# ECG_TRUE.net
KiCad netlist of a schematic drawn in EAGLE
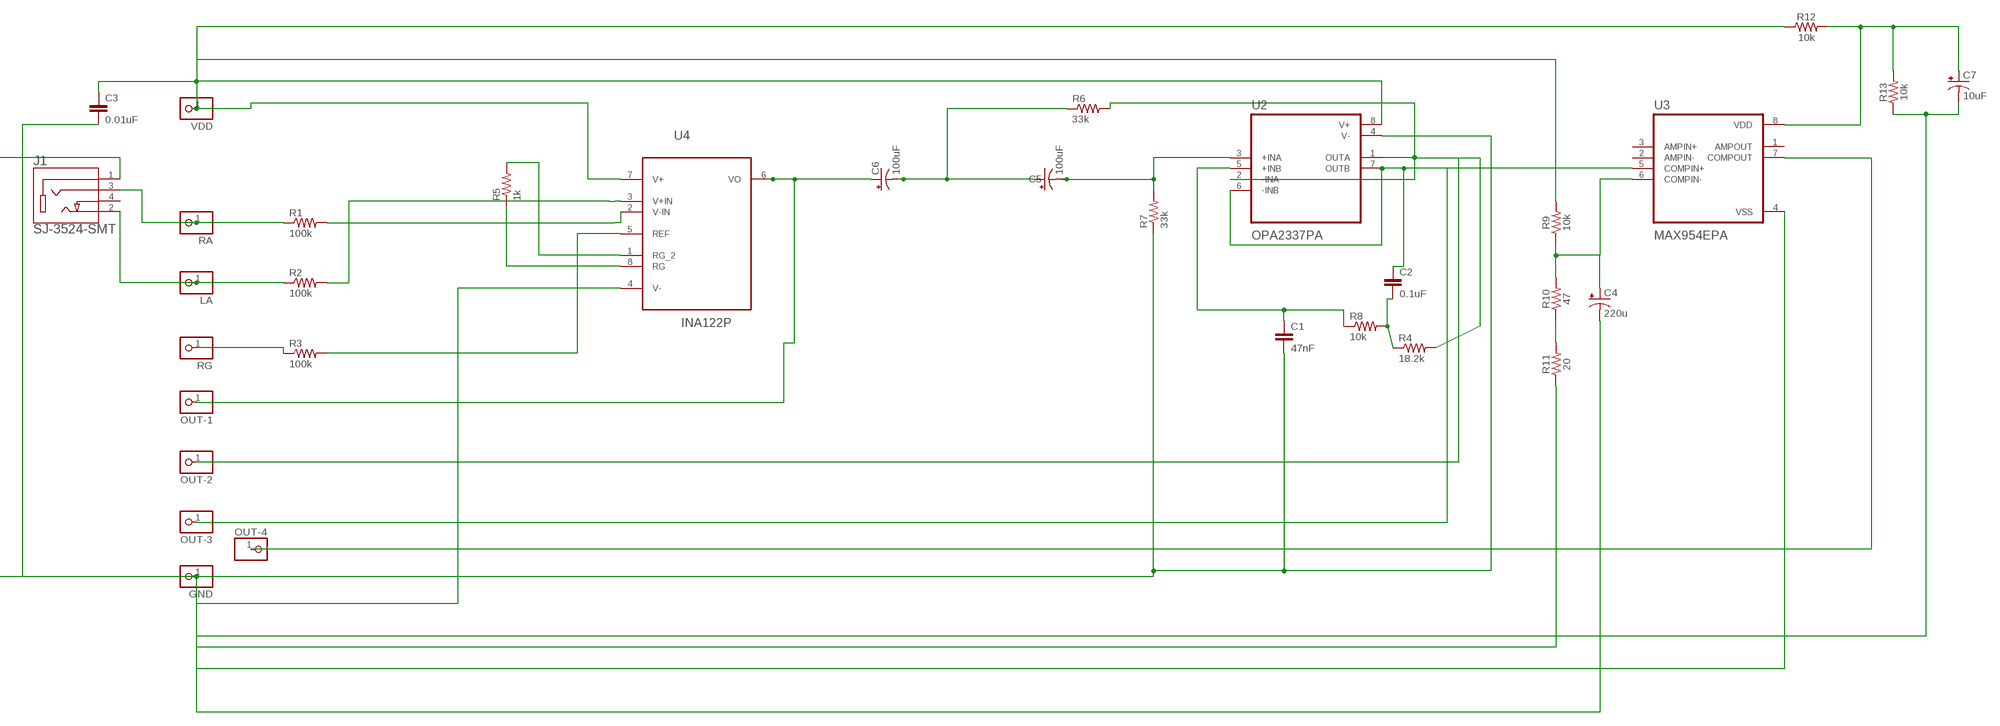
[diagram p0: schematic, sheet 1]

(export (version "E")
  (design (tool "Eeschema 10.0.6"))
  (components
    (comp (ref "C1")
      (value "47nF")
      (footprint "eagle-import:CAP-PTH-SMALL-KIT")
      (libsource (lib "eagle-import") (part "0.1UF-KIT-EZ-50V-20%"))
    )
    (comp (ref "C2")
      (value "0.1uF")
      (footprint "eagle-import:CAP-PTH-SMALL-KIT")
      (libsource (lib "eagle-import") (part "0.1UF-KIT-EZ-50V-20%"))
    )
    (comp (ref "C3")
      (value "0.01uF")
      (footprint "eagle-import:CAP-PTH-SMALL-KIT")
      (libsource (lib "eagle-import") (part "0.1UF-KIT-EZ-50V-20%"))
    )
    (comp (ref "C4")
      (value "220u")
      (footprint "eagle-import:E3,5-10")
      (libsource (lib "eagle-import") (part "CAPACITOR-PE3.5-10"))
    )
    (comp (ref "C5")
      (value "100uF")
      (footprint "eagle-import:CPOL-RADIAL-2.5MM-6.5MM")
      (libsource (lib "eagle-import") (part "100UF-POLAR-RADIAL-2.5MM-25V-20%"))
    )
    (comp (ref "C6")
      (value "100uF")
      (footprint "eagle-import:CPOL-RADIAL-2.5MM-6.5MM")
      (libsource (lib "eagle-import") (part "100UF-POLAR-RADIAL-2.5MM-25V-20%"))
    )
    (comp (ref "C7")
      (value "10uF")
      (footprint "eagle-import:CPOL-RADIAL-2.5MM-5MM-KIT")
      (libsource (lib "eagle-import") (part "10UF-POLAR-RADIAL-2.5MM-KIT-25V-20%"))
    )
    (comp (ref "GND")
      (value "PINHD-1X1")
      (footprint "eagle-import:1X01")
      (libsource (lib "eagle-import") (part "PINHD-1X1"))
    )
    (comp (ref "J1")
      (value "SJ-3524-SMT")
      (footprint "eagle-import:CUI_SJ-3524-SMT")
      (fields
        (field (name "DIGI-KEY_PART_NUMBER") "CP-3524SJCT-ND")
        (field (name "MF") "CUI Devices")
        (field (name "MP") "SJ-3524-SMT-TR")
      )
      (libsource (lib "eagle-import") (part "SJ-3524-SMT"))
    )
    (comp (ref "LA")
      (value "PINHD-1X1")
      (footprint "eagle-import:1X01")
      (libsource (lib "eagle-import") (part "PINHD-1X1"))
    )
    (comp (ref "OUT-1")
      (value "PINHD-1X1")
      (footprint "eagle-import:1X01")
      (libsource (lib "eagle-import") (part "PINHD-1X1"))
    )
    (comp (ref "OUT-2")
      (value "PINHD-1X1")
      (footprint "eagle-import:1X01")
      (libsource (lib "eagle-import") (part "PINHD-1X1"))
    )
    (comp (ref "OUT-3")
      (value "PINHD-1X1")
      (footprint "eagle-import:1X01")
      (libsource (lib "eagle-import") (part "PINHD-1X1"))
    )
    (comp (ref "OUT-4")
      (value "PINHD-1X1")
      (footprint "eagle-import:1X01")
      (libsource (lib "eagle-import") (part "PINHD-1X1"))
    )
    (comp (ref "R1")
      (value "100k")
      (footprint "eagle-import:AXIAL-0.3-KIT")
      (libsource (lib "eagle-import") (part "10KOHM-HORIZ_KIT-1/4W-1%"))
    )
    (comp (ref "R2")
      (value "100k")
      (footprint "eagle-import:AXIAL-0.3-KIT")
      (libsource (lib "eagle-import") (part "10KOHM-HORIZ_KIT-1/4W-1%"))
    )
    (comp (ref "R3")
      (value "100k")
      (footprint "eagle-import:AXIAL-0.3-KIT")
      (libsource (lib "eagle-import") (part "10KOHM-HORIZ_KIT-1/4W-1%"))
    )
    (comp (ref "R4")
      (value "18.2k")
      (footprint "eagle-import:AXIAL-0.3-KIT")
      (libsource (lib "eagle-import") (part "10KOHM-HORIZ_KIT-1/4W-1%"))
    )
    (comp (ref "R5")
      (value "1k")
      (footprint "eagle-import:AXIAL-0.3-KIT")
      (libsource (lib "eagle-import") (part "1KOHM-HORIZ_KIT-1/4W-1%"))
    )
    (comp (ref "R6")
      (value "33k")
      (footprint "eagle-import:AXIAL-0.3-KIT")
      (libsource (lib "eagle-import") (part "10KOHM-HORIZ_KIT-1/4W-1%"))
    )
    (comp (ref "R7")
      (value "33k")
      (footprint "eagle-import:AXIAL-0.3-KIT")
      (libsource (lib "eagle-import") (part "10KOHM-HORIZ_KIT-1/4W-1%"))
    )
    (comp (ref "R8")
      (value "10k")
      (footprint "eagle-import:AXIAL-0.3-KIT")
      (libsource (lib "eagle-import") (part "10KOHM-HORIZ_KIT-1/4W-1%"))
    )
    (comp (ref "R9")
      (value "10k")
      (footprint "eagle-import:AXIAL-0.3-KIT")
      (libsource (lib "eagle-import") (part "10KOHM-HORIZ_KIT-1/4W-1%"))
    )
    (comp (ref "R10")
      (value "47")
      (footprint "eagle-import:AXIAL-0.3-KIT")
      (libsource (lib "eagle-import") (part "10KOHM-HORIZ_KIT-1/4W-1%"))
    )
    (comp (ref "R11")
      (value "20")
      (footprint "eagle-import:AXIAL-0.3-KIT")
      (libsource (lib "eagle-import") (part "10KOHM-HORIZ_KIT-1/4W-1%"))
    )
    (comp (ref "R12")
      (value "10k")
      (footprint "eagle-import:AXIAL-0.3")
      (libsource (lib "eagle-import") (part "10KOHM-HORIZ-1/6W-5%"))
    )
    (comp (ref "R13")
      (value "10k")
      (footprint "eagle-import:AXIAL-0.3")
      (libsource (lib "eagle-import") (part "10KOHM-HORIZ-1/6W-5%"))
    )
    (comp (ref "RA")
      (value "PINHD-1X1")
      (footprint "eagle-import:1X01")
      (libsource (lib "eagle-import") (part "PINHD-1X1"))
    )
    (comp (ref "RG")
      (value "PINHD-1X1")
      (footprint "eagle-import:1X01")
      (libsource (lib "eagle-import") (part "PINHD-1X1"))
    )
    (comp (ref "U2")
      (value "OPA2337PA")
      (footprint "eagle-import:DIP794W45P254L1060H508Q8")
      (fields (field (name "MF") "Texas Instruments"))
      (libsource (lib "eagle-import") (part "OPA2337PA"))
    )
    (comp (ref "U3")
      (value "MAX954EPA")
      (footprint "eagle-import:DIP794W47P254L991H457Q8")
      (fields
        (field (name "DIGI-KEY_PART_NUMBER") "MAX954EPA+-ND")
        (field (name "MF") "Maxim Integrated")
        (field (name "MP") "MAX954EPA+")
      )
      (libsource (lib "eagle-import") (part "MAX954EPA"))
    )
    (comp (ref "U4")
      (value "INA122P")
      (footprint "eagle-import:DIP254P762X508-8")
      (fields (field (name "DIGI-KEY_PART_NUMBER") "INA122P-ND") (field (name "MF") "Texas Instruments"))
      (libsource (lib "eagle-import") (part "INA122P"))
    )
    (comp (ref "VDD")
      (value "PINHD-1X1")
      (footprint "eagle-import:1X01")
      (libsource (lib "eagle-import") (part "PINHD-1X1"))
    )
  )
  (nets
    (net (code "1") (name "Net-(C5-+)") (class "Default")
      (node (ref "C5") (pin "1") (pinfunction "+_1") (pintype "passive"))
      (node (ref "C6") (pin "2") (pinfunction "-_2") (pintype "passive"))
      (node (ref "R6") (pin "P$1") (pinfunction "1_P$1") (pintype "passive"))
    )
    (net (code "2") (name "Net-(C5--)") (class "Default")
      (node (ref "C5") (pin "2") (pinfunction "-_2") (pintype "passive"))
      (node (ref "R7") (pin "P$2") (pinfunction "2_P$2") (pintype "passive"))
      (node (ref "U2") (pin "3") (pinfunction "+INA_3") (pintype "input"))
    )
    (net (code "3") (name "Net-(C6-+)") (class "Default")
      (node (ref "C6") (pin "1") (pinfunction "+_1") (pintype "passive"))
      (node (ref "OUT-1") (pin "1") (pinfunction "1_1") (pintype "passive"))
      (node (ref "U4") (pin "6") (pinfunction "VO_6") (pintype "output"))
    )
    (net (code "4") (name "Net-(C7-+)") (class "Default")
      (node (ref "C7") (pin "1") (pinfunction "+_1") (pintype "passive"))
      (node (ref "R12") (pin "P$2") (pinfunction "2_P$2") (pintype "passive"))
      (node (ref "R13") (pin "P$2") (pinfunction "2_P$2") (pintype "passive"))
      (node (ref "U3") (pin "8") (pinfunction "VDD_8") (pintype "power_in"))
    )
    (net (code "5") (name "Net-(C7--)") (class "Default")
      (node (ref "C1") (pin "2") (pinfunction "2_2") (pintype "passive"))
      (node (ref "C3") (pin "2") (pinfunction "2_2") (pintype "passive"))
      (node (ref "C4") (pin "-") (pinfunction "-_-") (pintype "passive"))
      (node (ref "C7") (pin "2") (pinfunction "-_2") (pintype "passive"))
      (node (ref "GND") (pin "1") (pinfunction "1_1") (pintype "passive"))
      (node (ref "J1") (pin "1") (pinfunction "1_1") (pintype "passive"))
      (node (ref "R11") (pin "P$1") (pinfunction "1_P$1") (pintype "passive"))
      (node (ref "R13") (pin "P$1") (pinfunction "1_P$1") (pintype "passive"))
      (node (ref "R7") (pin "P$1") (pinfunction "1_P$1") (pintype "passive"))
      (node (ref "U2") (pin "4") (pinfunction "V-_4") (pintype "power_in"))
      (node (ref "U3") (pin "4") (pinfunction "VSS_4") (pintype "power_in"))
      (node (ref "U4") (pin "4") (pinfunction "V-_4") (pintype "power_in"))
    )
    (net (code "6") (name "Net-(R1-1)") (class "Default")
      (node (ref "J1") (pin "3") (pinfunction "3_3") (pintype "passive"))
      (node (ref "R1") (pin "P$1") (pinfunction "1_P$1") (pintype "passive"))
      (node (ref "RA") (pin "1") (pinfunction "1_1") (pintype "passive"))
    )
    (net (code "7") (name "Net-(R1-2)") (class "Default")
      (node (ref "R1") (pin "P$2") (pinfunction "2_P$2") (pintype "passive"))
      (node (ref "U4") (pin "2") (pinfunction "V-IN_2") (pintype "input"))
    )
    (net (code "8") (name "Net-(R2-1)") (class "Default")
      (node (ref "J1") (pin "2") (pinfunction "2_2") (pintype "passive"))
      (node (ref "LA") (pin "1") (pinfunction "1_1") (pintype "passive"))
      (node (ref "R2") (pin "P$1") (pinfunction "1_P$1") (pintype "passive"))
    )
    (net (code "9") (name "Net-(R2-2)") (class "Default")
      (node (ref "R2") (pin "P$2") (pinfunction "2_P$2") (pintype "passive"))
      (node (ref "U4") (pin "3") (pinfunction "V+IN_3") (pintype "input"))
    )
    (net (code "10") (name "Net-(R3-1)") (class "Default")
      (node (ref "R3") (pin "P$1") (pinfunction "1_P$1") (pintype "passive"))
      (node (ref "RG") (pin "1") (pinfunction "1_1") (pintype "passive"))
    )
    (net (code "11") (name "Net-(R3-2)") (class "Default")
      (node (ref "R3") (pin "P$2") (pinfunction "2_P$2") (pintype "passive"))
      (node (ref "U4") (pin "5") (pinfunction "REF_5") (pintype "passive"))
    )
    (net (code "12") (name "Net-(R4-1)") (class "Default")
      (node (ref "C2") (pin "2") (pinfunction "2_2") (pintype "passive"))
      (node (ref "R4") (pin "P$1") (pinfunction "1_P$1") (pintype "passive"))
      (node (ref "R8") (pin "P$2") (pinfunction "2_P$2") (pintype "passive"))
    )
    (net (code "13") (name "Net-(R4-2)") (class "Default")
      (node (ref "OUT-2") (pin "1") (pinfunction "1_1") (pintype "passive"))
      (node (ref "R4") (pin "P$2") (pinfunction "2_P$2") (pintype "passive"))
      (node (ref "R6") (pin "P$2") (pinfunction "2_P$2") (pintype "passive"))
      (node (ref "U2") (pin "1") (pinfunction "OUTA_1") (pintype "output"))
      (node (ref "U2") (pin "2") (pinfunction "-INA_2") (pintype "input"))
    )
    (net (code "14") (name "Net-(R5-1)") (class "Default")
      (node (ref "R5") (pin "P$1") (pinfunction "1_P$1") (pintype "passive"))
      (node (ref "U4") (pin "8") (pinfunction "RG_8") (pintype "passive"))
    )
    (net (code "15") (name "Net-(R5-2)") (class "Default")
      (node (ref "R5") (pin "P$2") (pinfunction "2_P$2") (pintype "passive"))
      (node (ref "U4") (pin "1") (pinfunction "RG_2_1") (pintype "passive"))
    )
    (net (code "16") (name "Net-(R8-1)") (class "Default")
      (node (ref "C1") (pin "1") (pinfunction "1_1") (pintype "passive"))
      (node (ref "R8") (pin "P$1") (pinfunction "1_P$1") (pintype "passive"))
      (node (ref "U2") (pin "5") (pinfunction "+INB_5") (pintype "input"))
    )
    (net (code "17") (name "Net-(R10-1)") (class "Default")
      (node (ref "R10") (pin "P$1") (pinfunction "1_P$1") (pintype "passive"))
      (node (ref "R11") (pin "P$2") (pinfunction "2_P$2") (pintype "passive"))
    )
    (net (code "18") (name "Net-(R10-2)") (class "Default")
      (node (ref "C4") (pin "+") (pinfunction "+_+") (pintype "passive"))
      (node (ref "R10") (pin "P$2") (pinfunction "2_P$2") (pintype "passive"))
      (node (ref "R9") (pin "P$1") (pinfunction "1_P$1") (pintype "passive"))
      (node (ref "U3") (pin "6") (pinfunction "COMPIN-_6") (pintype "input"))
    )
    (net (code "19") (name "Net-(R12-1)") (class "Default")
      (node (ref "C3") (pin "1") (pinfunction "1_1") (pintype "passive"))
      (node (ref "R12") (pin "P$1") (pinfunction "1_P$1") (pintype "passive"))
      (node (ref "R9") (pin "P$2") (pinfunction "2_P$2") (pintype "passive"))
      (node (ref "U2") (pin "8") (pinfunction "V+_8") (pintype "power_in"))
      (node (ref "U4") (pin "7") (pinfunction "V+_7") (pintype "power_in"))
      (node (ref "VDD") (pin "1") (pinfunction "1_1") (pintype "passive"))
    )
    (net (code "20") (name "Net-(U2--INB)") (class "Default")
      (node (ref "C2") (pin "1") (pinfunction "1_1") (pintype "passive"))
      (node (ref "OUT-3") (pin "1") (pinfunction "1_1") (pintype "passive"))
      (node (ref "U2") (pin "6") (pinfunction "-INB_6") (pintype "input"))
      (node (ref "U2") (pin "7") (pinfunction "OUTB_7") (pintype "output"))
      (node (ref "U3") (pin "5") (pinfunction "COMPIN+_5") (pintype "input"))
    )
    (net (code "21") (name "Net-(U3-COMPOUT)") (class "Default")
      (node (ref "OUT-4") (pin "1") (pinfunction "1_1") (pintype "passive"))
      (node (ref "U3") (pin "7") (pinfunction "COMPOUT_7") (pintype "output"))
    )
    (net (code "22") (name "unconnected-(J1-Pad4)") (class "Default")
      (node (ref "J1") (pin "4") (pinfunction "4_4") (pintype "passive"))
    )
    (net (code "23") (name "unconnected-(U3-AMPIN+-Pad3)") (class "Default")
      (node (ref "U3") (pin "3") (pinfunction "AMPIN+_3") (pintype "input"))
    )
    (net (code "24") (name "unconnected-(U3-AMPIN--Pad2)") (class "Default")
      (node (ref "U3") (pin "2") (pinfunction "AMPIN-_2") (pintype "input"))
    )
    (net (code "25") (name "unconnected-(U3-AMPOUT-Pad1)") (class "Default")
      (node (ref "U3") (pin "1") (pinfunction "AMPOUT_1") (pintype "output"))
    )
  )
)
